# iomodul2.net
KiCad netlist of a schematic drawn in EAGLE
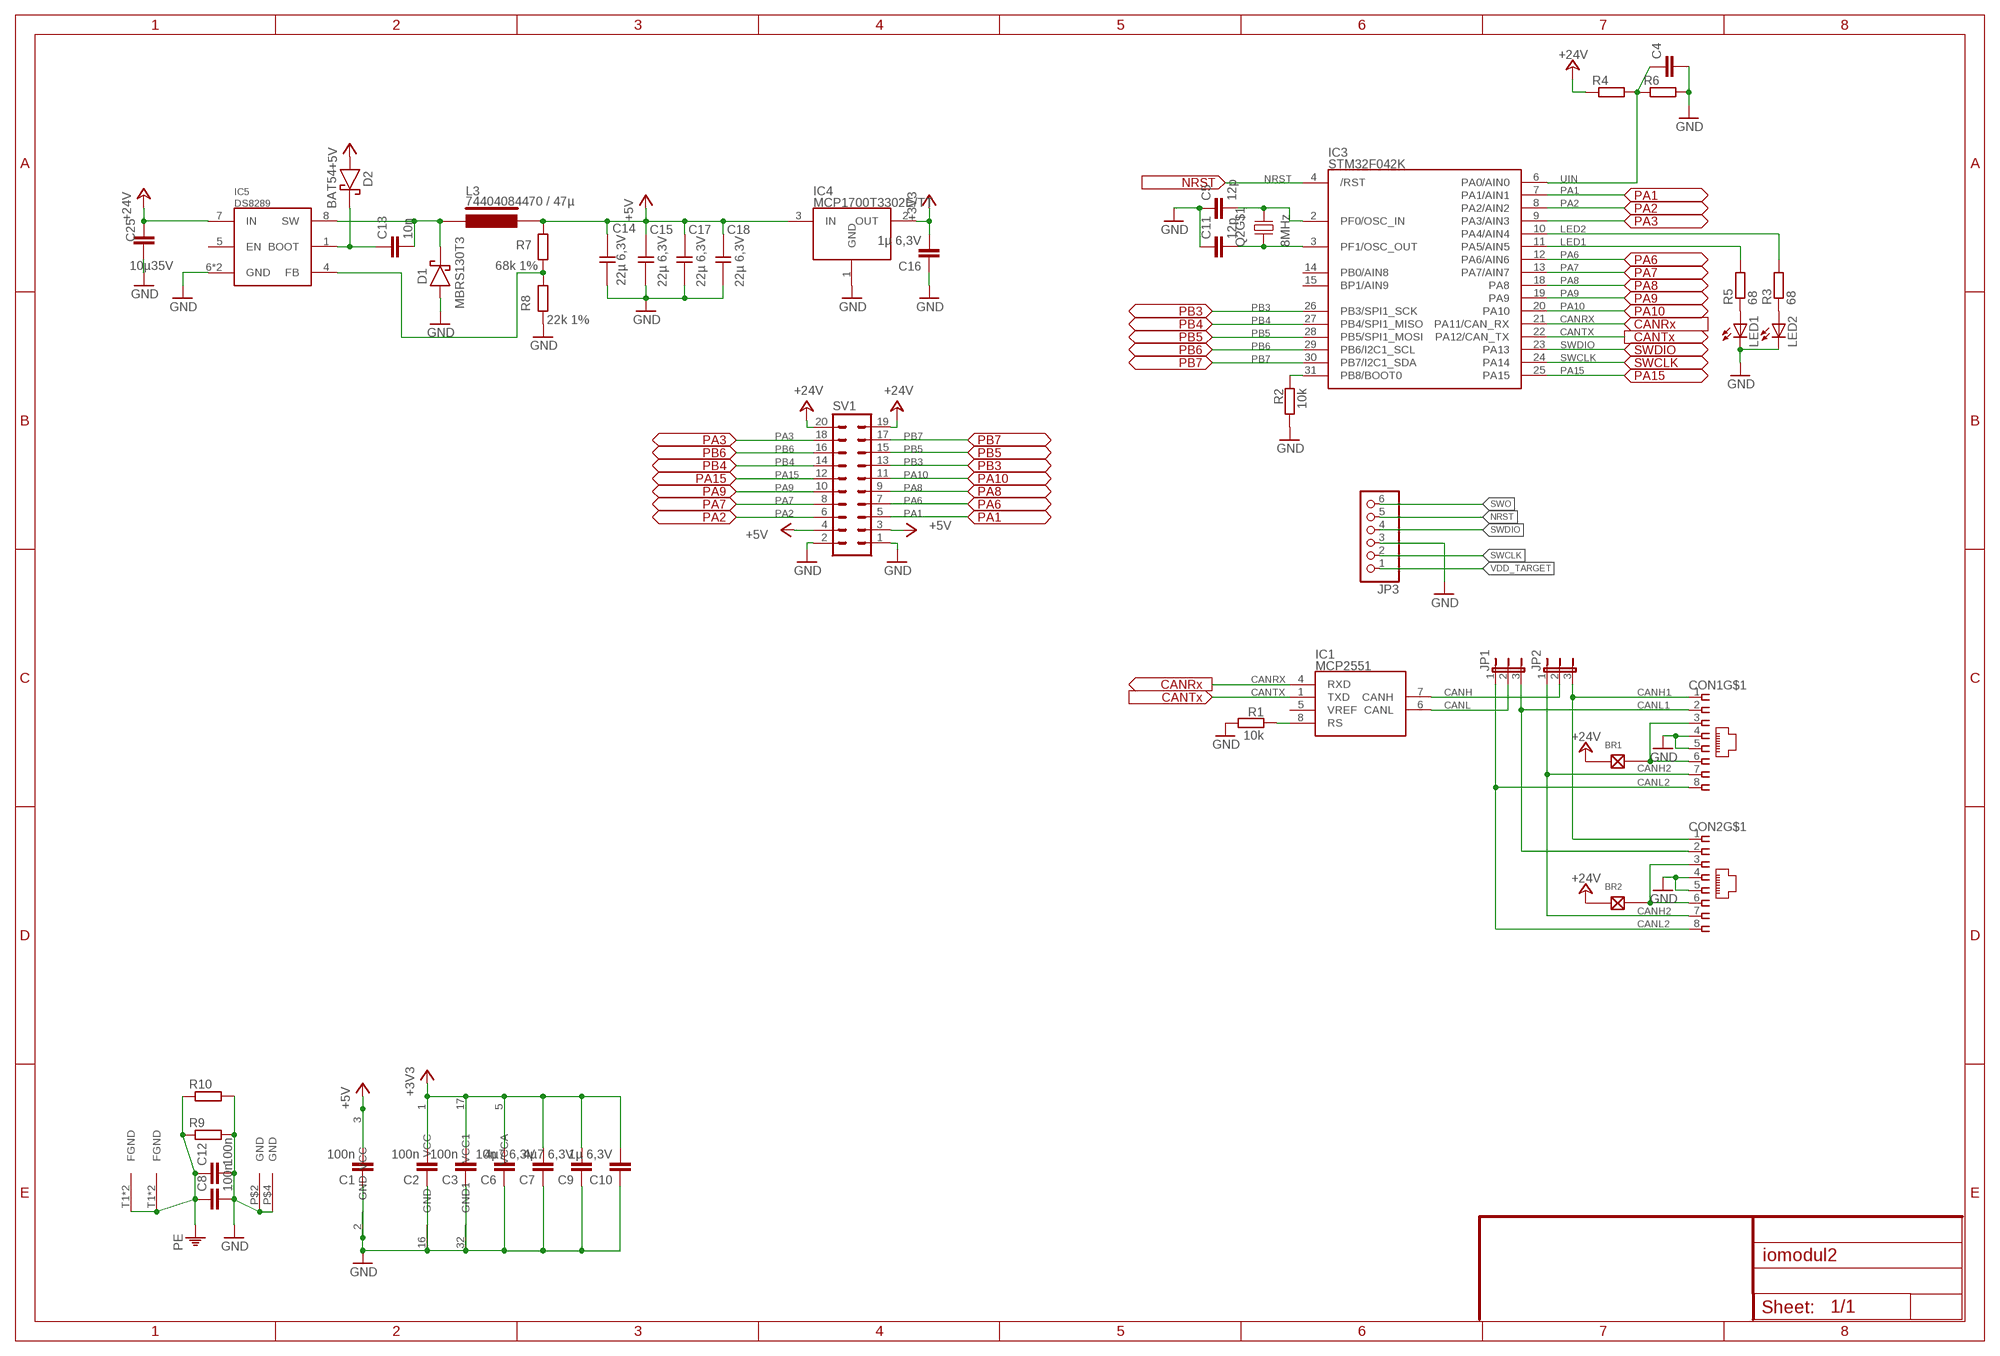
[diagram p0: schematic, sheet 1]

(export (version "E")
  (design (tool "Eeschema 10.0.6"))
  (components
    (comp (ref "BR1")
      (value "LÖTBRÜCKE-S")
      (footprint "eagle-import:LÖTBRÜCKE")
      (libsource (lib "eagle-import") (part "LÖTBRÜCKE-S"))
    )
    (comp (ref "BR2")
      (value "LÖTBRÜCKE-S")
      (footprint "eagle-import:LÖTBRÜCKE")
      (libsource (lib "eagle-import") (part "LÖTBRÜCKE-S"))
    )
    (comp (ref "C1")
      (value "100n")
      (footprint "eagle-import:C1206")
      (libsource (lib "eagle-import") (part "C-EUC1206"))
    )
    (comp (ref "C2")
      (value "100n")
      (footprint "eagle-import:C1206")
      (libsource (lib "eagle-import") (part "C-EUC1206"))
    )
    (comp (ref "C3")
      (value "100n")
      (footprint "eagle-import:C1206")
      (libsource (lib "eagle-import") (part "C-EUC1206"))
    )
    (comp (ref "C4")
      (value "C-EUC1206")
      (footprint "eagle-import:C1206")
      (libsource (lib "eagle-import") (part "C-EUC1206"))
    )
    (comp (ref "C5")
      (value "12p")
      (footprint "eagle-import:C1206")
      (libsource (lib "eagle-import") (part "C-EUC1206"))
    )
    (comp (ref "C6")
      (value "10n")
      (footprint "eagle-import:C1206")
      (libsource (lib "eagle-import") (part "C-EUC1206"))
    )
    (comp (ref "C7")
      (value "4µ7 6,3V")
      (footprint "eagle-import:C1206")
      (libsource (lib "eagle-import") (part "C-EUC1206"))
    )
    (comp (ref "C8")
      (value "100n")
      (footprint "eagle-import:C1206")
      (libsource (lib "eagle-import") (part "C-EUC1206"))
    )
    (comp (ref "C9")
      (value "4µ7 6,3V")
      (footprint "eagle-import:C1206")
      (libsource (lib "eagle-import") (part "C-EUC1206"))
    )
    (comp (ref "C10")
      (value "1µ 6,3V")
      (footprint "eagle-import:C1206")
      (libsource (lib "eagle-import") (part "C-EUC1206"))
    )
    (comp (ref "C11")
      (value "12p")
      (footprint "eagle-import:C1206")
      (libsource (lib "eagle-import") (part "C-EUC1206"))
    )
    (comp (ref "C12")
      (value "100n")
      (footprint "eagle-import:C1206")
      (libsource (lib "eagle-import") (part "C-EUC1206"))
    )
    (comp (ref "C13")
      (value "10n")
      (footprint "eagle-import:C1206")
      (libsource (lib "eagle-import") (part "C-EUC1206"))
    )
    (comp (ref "C14")
      (value "22µ 6,3V")
      (footprint "eagle-import:1210")
      (libsource (lib "eagle-import") (part "CAP1210"))
    )
    (comp (ref "C15")
      (value "22µ 6,3V")
      (footprint "eagle-import:1210")
      (libsource (lib "eagle-import") (part "CAP1210"))
    )
    (comp (ref "C16")
      (value "1µ 6,3V")
      (footprint "eagle-import:C1206")
      (libsource (lib "eagle-import") (part "C-EUC1206"))
    )
    (comp (ref "C17")
      (value "22µ 6,3V")
      (footprint "eagle-import:1210")
      (libsource (lib "eagle-import") (part "CAP1210"))
    )
    (comp (ref "C18")
      (value "22µ 6,3V")
      (footprint "eagle-import:1210")
      (libsource (lib "eagle-import") (part "CAP1210"))
    )
    (comp (ref "C25")
      (value "10µ35V")
      (footprint "eagle-import:C1206")
      (libsource (lib "eagle-import") (part "C-EUC1206"))
    )
    (comp (ref "CON1")
      (value "MEBP_8-8G")
      (footprint "eagle-import:MEBP")
      (libsource (lib "eagle-import") (part "MEBP_8-8G"))
    )
    (comp (ref "CON2")
      (value "MEBP_8-8G")
      (footprint "eagle-import:MEBP")
      (libsource (lib "eagle-import") (part "MEBP_8-8G"))
    )
    (comp (ref "D1")
      (value "MBRS130T3")
      (footprint "eagle-import:SMB")
      (libsource (lib "eagle-import") (part "MBRS130T3"))
    )
    (comp (ref "D2")
      (value "BAT54")
      (footprint "eagle-import:SOT23_32")
      (libsource (lib "eagle-import") (part "BAT54"))
    )
    (comp (ref "IC1")
      (value "MCP2551")
      (footprint "eagle-import:SO-8")
      (libsource (lib "eagle-import") (part "MCP2551"))
    )
    (comp (ref "IC3")
      (value "STM32F042K")
      (footprint "eagle-import:LQFP32")
      (libsource (lib "eagle-import") (part "STM32F042"))
    )
    (comp (ref "IC4")
      (value "MCP1700T3302E/TT")
      (footprint "eagle-import:SOT23")
      (libsource (lib "eagle-import") (part "MCP1700"))
    )
    (comp (ref "IC5")
      (value "DS8289")
      (footprint "eagle-import:SO8-POWERPAD")
      (libsource (lib "eagle-import") (part "DS8289"))
    )
    (comp (ref "JP1")
      (value "JP2E")
      (footprint "eagle-import:JP2")
      (libsource (lib "eagle-import") (part "JP2E"))
    )
    (comp (ref "JP2")
      (value "JP2E")
      (footprint "eagle-import:JP2")
      (libsource (lib "eagle-import") (part "JP2E"))
    )
    (comp (ref "JP3")
      (value "PINHD-1X6")
      (footprint "eagle-import:1X06")
      (libsource (lib "eagle-import") (part "PINHD-1X6"))
    )
    (comp (ref "L3")
      (value "74404084470 / 47µ")
      (footprint "eagle-import:WE-LQS")
      (libsource (lib "eagle-import") (part "WE-LQS"))
    )
    (comp (ref "LED1")
      (value "LEDCHIPLED_0603")
      (footprint "eagle-import:CHIPLED_0603")
      (libsource (lib "eagle-import") (part "LEDCHIPLED_0603"))
    )
    (comp (ref "LED2")
      (value "LEDCHIPLED_0603")
      (footprint "eagle-import:CHIPLED_0603")
      (libsource (lib "eagle-import") (part "LEDCHIPLED_0603"))
    )
    (comp (ref "Q2")
      (value "8MHz")
      (footprint "eagle-import:MT-CRYSTAL")
      (libsource (lib "eagle-import") (part "MT-CRYSTAL"))
    )
    (comp (ref "R1")
      (value "10k")
      (footprint "eagle-import:R1206")
      (libsource (lib "eagle-import") (part "R-EU_R1206"))
    )
    (comp (ref "R2")
      (value "10k")
      (footprint "eagle-import:R1206")
      (libsource (lib "eagle-import") (part "R-EU_R1206"))
    )
    (comp (ref "R3")
      (value "68")
      (footprint "eagle-import:R1206")
      (libsource (lib "eagle-import") (part "R-EU_R1206"))
    )
    (comp (ref "R4")
      (value "R-EU_R1206")
      (footprint "eagle-import:R1206")
      (libsource (lib "eagle-import") (part "R-EU_R1206"))
    )
    (comp (ref "R5")
      (value "68")
      (footprint "eagle-import:R1206")
      (libsource (lib "eagle-import") (part "R-EU_R1206"))
    )
    (comp (ref "R6")
      (value "R-EU_R1206")
      (footprint "eagle-import:R1206")
      (libsource (lib "eagle-import") (part "R-EU_R1206"))
    )
    (comp (ref "R7")
      (value "68k 1%")
      (footprint "eagle-import:R1206")
      (libsource (lib "eagle-import") (part "R-EU_R1206"))
    )
    (comp (ref "R8")
      (value "22k 1%")
      (footprint "eagle-import:R1206")
      (libsource (lib "eagle-import") (part "R-EU_R1206"))
    )
    (comp (ref "R9")
      (value "R-EU_R1206")
      (footprint "eagle-import:R1206")
      (libsource (lib "eagle-import") (part "R-EU_R1206"))
    )
    (comp (ref "R10")
      (value "R-EU_R1206")
      (footprint "eagle-import:R1206")
      (libsource (lib "eagle-import") (part "R-EU_R1206"))
    )
    (comp (ref "SV1")
      (value "MA10-2")
      (footprint "eagle-import:MA10-2")
      (libsource (lib "eagle-import") (part "MA10-2"))
    )
  )
  (nets
    (net (code "1") (name "+3V3") (class "Default")
      (node (ref "C10") (pin "2") (pinfunction "2_2") (pintype "passive"))
      (node (ref "C16") (pin "2") (pinfunction "2_2") (pintype "passive"))
      (node (ref "C2") (pin "2") (pinfunction "2_2") (pintype "passive"))
      (node (ref "C3") (pin "2") (pinfunction "2_2") (pintype "passive"))
      (node (ref "C6") (pin "2") (pinfunction "2_2") (pintype "passive"))
      (node (ref "C7") (pin "2") (pinfunction "2_2") (pintype "passive"))
      (node (ref "C9") (pin "2") (pinfunction "2_2") (pintype "passive"))
      (node (ref "IC3") (pin "1") (pinfunction "VCC_1") (pintype "power_in"))
      (node (ref "IC3") (pin "17") (pinfunction "VCC1_17") (pintype "power_in"))
      (node (ref "IC3") (pin "5") (pinfunction "VCCA_5") (pintype "power_in"))
      (node (ref "IC4") (pin "2") (pinfunction "OUT_2") (pintype "power_in"))
    )
    (net (code "2") (name "+5V") (class "Default")
      (node (ref "C1") (pin "2") (pinfunction "2_2") (pintype "passive"))
      (node (ref "C14") (pin "2") (pinfunction "2_2") (pintype "passive"))
      (node (ref "C15") (pin "2") (pinfunction "2_2") (pintype "passive"))
      (node (ref "C17") (pin "2") (pinfunction "2_2") (pintype "passive"))
      (node (ref "C18") (pin "2") (pinfunction "2_2") (pintype "passive"))
      (node (ref "D2") (pin "1") (pinfunction "A_1") (pintype "passive"))
      (node (ref "IC1") (pin "3") (pinfunction "VCC_3") (pintype "power_in"))
      (node (ref "IC4") (pin "3") (pinfunction "IN_3") (pintype "power_in"))
      (node (ref "L3") (pin "P$2") (pinfunction "P$2_P$2") (pintype "passive"))
      (node (ref "R7") (pin "2") (pinfunction "2_2") (pintype "passive"))
      (node (ref "SV1") (pin "3") (pinfunction "3_3") (pintype "passive"))
      (node (ref "SV1") (pin "4") (pinfunction "4_4") (pintype "passive"))
    )
    (net (code "3") (name "+24V") (class "Default")
      (node (ref "BR1") (pin "1") (pinfunction "1_1") (pintype "passive"))
      (node (ref "BR2") (pin "1") (pinfunction "1_1") (pintype "passive"))
      (node (ref "C25") (pin "2") (pinfunction "2_2") (pintype "passive"))
      (node (ref "IC5") (pin "7") (pinfunction "IN_7") (pintype "power_in"))
      (node (ref "R4") (pin "1") (pinfunction "1_1") (pintype "passive"))
      (node (ref "SV1") (pin "19") (pinfunction "19_19") (pintype "passive"))
      (node (ref "SV1") (pin "20") (pinfunction "20_20") (pintype "passive"))
    )
    (net (code "4") (name "/CANH") (class "Default")
      (node (ref "IC1") (pin "7") (pinfunction "CANH_7") (pintype "bidirectional"))
      (node (ref "JP2") (pin "2") (pinfunction "2_2") (pintype "passive"))
    )
    (net (code "5") (name "/CANH1") (class "Default")
      (node (ref "CON1") (pin "1") (pinfunction "1_1") (pintype "passive"))
      (node (ref "CON2") (pin "1") (pinfunction "1_1") (pintype "passive"))
      (node (ref "JP2") (pin "3") (pinfunction "3_3") (pintype "passive"))
    )
    (net (code "6") (name "/CANH2") (class "Default")
      (node (ref "CON1") (pin "7") (pinfunction "7_7") (pintype "passive"))
      (node (ref "CON2") (pin "7") (pinfunction "7_7") (pintype "passive"))
      (node (ref "JP2") (pin "1") (pinfunction "1_1") (pintype "passive"))
    )
    (net (code "7") (name "/CANL") (class "Default")
      (node (ref "IC1") (pin "6") (pinfunction "CANL_6") (pintype "bidirectional"))
      (node (ref "JP1") (pin "2") (pinfunction "2_2") (pintype "passive"))
    )
    (net (code "8") (name "/CANL1") (class "Default")
      (node (ref "CON1") (pin "2") (pinfunction "2_2") (pintype "passive"))
      (node (ref "CON2") (pin "2") (pinfunction "2_2") (pintype "passive"))
      (node (ref "JP1") (pin "3") (pinfunction "3_3") (pintype "passive"))
    )
    (net (code "9") (name "/CANL2") (class "Default")
      (node (ref "CON1") (pin "8") (pinfunction "8_8") (pintype "passive"))
      (node (ref "CON2") (pin "8") (pinfunction "8_8") (pintype "passive"))
      (node (ref "JP1") (pin "1") (pinfunction "1_1") (pintype "passive"))
    )
    (net (code "10") (name "/CANRX") (class "Default")
      (node (ref "IC1") (pin "4") (pinfunction "RXD_4") (pintype "bidirectional"))
      (node (ref "IC3") (pin "21") (pinfunction "PA11/CAN_RX_21") (pintype "bidirectional"))
    )
    (net (code "11") (name "/CANTX") (class "Default")
      (node (ref "IC1") (pin "1") (pinfunction "TXD_1") (pintype "bidirectional"))
      (node (ref "IC3") (pin "22") (pinfunction "PA12/CAN_TX_22") (pintype "bidirectional"))
    )
    (net (code "12") (name "/LED1") (class "Default")
      (node (ref "IC3") (pin "11") (pinfunction "PA5/AIN5_11") (pintype "bidirectional"))
      (node (ref "R5") (pin "2") (pinfunction "2_2") (pintype "passive"))
    )
    (net (code "13") (name "/LED2") (class "Default")
      (node (ref "IC3") (pin "10") (pinfunction "PA4/AIN4_10") (pintype "bidirectional"))
      (node (ref "R3") (pin "2") (pinfunction "2_2") (pintype "passive"))
    )
    (net (code "14") (name "/PA1") (class "Default")
      (node (ref "IC3") (pin "7") (pinfunction "PA1/AIN1_7") (pintype "bidirectional"))
      (node (ref "SV1") (pin "5") (pinfunction "5_5") (pintype "passive"))
    )
    (net (code "15") (name "/PA2") (class "Default")
      (node (ref "IC3") (pin "8") (pinfunction "PA2/AIN2_8") (pintype "bidirectional"))
      (node (ref "SV1") (pin "6") (pinfunction "6_6") (pintype "passive"))
    )
    (net (code "16") (name "/PA3") (class "Default")
      (node (ref "IC3") (pin "9") (pinfunction "PA3/AIN3_9") (pintype "bidirectional"))
      (node (ref "SV1") (pin "18") (pinfunction "18_18") (pintype "passive"))
    )
    (net (code "17") (name "/PA6") (class "Default")
      (node (ref "IC3") (pin "12") (pinfunction "PA6/AIN6_12") (pintype "bidirectional"))
      (node (ref "SV1") (pin "7") (pinfunction "7_7") (pintype "passive"))
    )
    (net (code "18") (name "/PA7") (class "Default")
      (node (ref "IC3") (pin "13") (pinfunction "PA7/AIN7_13") (pintype "bidirectional"))
      (node (ref "SV1") (pin "8") (pinfunction "8_8") (pintype "passive"))
    )
    (net (code "19") (name "/PA8") (class "Default")
      (node (ref "IC3") (pin "18") (pinfunction "PA8_18") (pintype "bidirectional"))
      (node (ref "SV1") (pin "9") (pinfunction "9_9") (pintype "passive"))
    )
    (net (code "20") (name "/PA9") (class "Default")
      (node (ref "IC3") (pin "19") (pinfunction "PA9_19") (pintype "bidirectional"))
      (node (ref "SV1") (pin "10") (pinfunction "10_10") (pintype "passive"))
    )
    (net (code "21") (name "/PA10") (class "Default")
      (node (ref "IC3") (pin "20") (pinfunction "PA10_20") (pintype "bidirectional"))
      (node (ref "SV1") (pin "11") (pinfunction "11_11") (pintype "passive"))
    )
    (net (code "22") (name "/PA15") (class "Default")
      (node (ref "IC3") (pin "25") (pinfunction "PA15_25") (pintype "bidirectional"))
      (node (ref "SV1") (pin "12") (pinfunction "12_12") (pintype "passive"))
    )
    (net (code "23") (name "/PB3") (class "Default")
      (node (ref "IC3") (pin "26") (pinfunction "PB3/SPI1_SCK_26") (pintype "bidirectional"))
      (node (ref "SV1") (pin "13") (pinfunction "13_13") (pintype "passive"))
    )
    (net (code "24") (name "/PB4") (class "Default")
      (node (ref "IC3") (pin "27") (pinfunction "PB4/SPI1_MISO_27") (pintype "bidirectional"))
      (node (ref "SV1") (pin "14") (pinfunction "14_14") (pintype "passive"))
    )
    (net (code "25") (name "/PB5") (class "Default")
      (node (ref "IC3") (pin "28") (pinfunction "PB5/SPI1_MOSI_28") (pintype "bidirectional"))
      (node (ref "SV1") (pin "15") (pinfunction "15_15") (pintype "passive"))
    )
    (net (code "26") (name "/PB6") (class "Default")
      (node (ref "IC3") (pin "29") (pinfunction "PB6/I2C1_SCL_29") (pintype "bidirectional"))
      (node (ref "SV1") (pin "16") (pinfunction "16_16") (pintype "passive"))
    )
    (net (code "27") (name "/PB7") (class "Default")
      (node (ref "IC3") (pin "30") (pinfunction "PB7/I2C1_SDA_30") (pintype "bidirectional"))
      (node (ref "SV1") (pin "17") (pinfunction "17_17") (pintype "passive"))
    )
    (net (code "28") (name "/UIN") (class "Default")
      (node (ref "C4") (pin "1") (pinfunction "1_1") (pintype "passive"))
      (node (ref "IC3") (pin "6") (pinfunction "PA0/AIN0_6") (pintype "bidirectional"))
      (node (ref "R4") (pin "2") (pinfunction "2_2") (pintype "passive"))
      (node (ref "R6") (pin "1") (pinfunction "1_1") (pintype "passive"))
    )
    (net (code "29") (name "GND") (class "Default")
      (node (ref "C1") (pin "1") (pinfunction "1_1") (pintype "passive"))
      (node (ref "C10") (pin "1") (pinfunction "1_1") (pintype "passive"))
      (node (ref "C11") (pin "1") (pinfunction "1_1") (pintype "passive"))
      (node (ref "C12") (pin "2") (pinfunction "2_2") (pintype "passive"))
      (node (ref "C14") (pin "1") (pinfunction "1_1") (pintype "passive"))
      (node (ref "C15") (pin "1") (pinfunction "1_1") (pintype "passive"))
      (node (ref "C16") (pin "1") (pinfunction "1_1") (pintype "passive"))
      (node (ref "C17") (pin "1") (pinfunction "1_1") (pintype "passive"))
      (node (ref "C18") (pin "1") (pinfunction "1_1") (pintype "passive"))
      (node (ref "C2") (pin "1") (pinfunction "1_1") (pintype "passive"))
      (node (ref "C25") (pin "1") (pinfunction "1_1") (pintype "passive"))
      (node (ref "C3") (pin "1") (pinfunction "1_1") (pintype "passive"))
      (node (ref "C4") (pin "2") (pinfunction "2_2") (pintype "passive"))
      (node (ref "C5") (pin "1") (pinfunction "1_1") (pintype "passive"))
      (node (ref "C6") (pin "1") (pinfunction "1_1") (pintype "passive"))
      (node (ref "C7") (pin "1") (pinfunction "1_1") (pintype "passive"))
      (node (ref "C8") (pin "2") (pinfunction "2_2") (pintype "passive"))
      (node (ref "C9") (pin "1") (pinfunction "1_1") (pintype "passive"))
      (node (ref "CON1") (pin "4") (pinfunction "4_4") (pintype "passive"))
      (node (ref "CON1") (pin "5") (pinfunction "5_5") (pintype "passive"))
      (node (ref "CON2") (pin "4") (pinfunction "4_4") (pintype "passive"))
      (node (ref "CON2") (pin "5") (pinfunction "5_5") (pintype "passive"))
      (node (ref "D1") (pin "A") (pinfunction "A_A") (pintype "passive"))
      (node (ref "IC1") (pin "2") (pinfunction "GND_2") (pintype "power_in"))
      (node (ref "IC3") (pin "16") (pinfunction "GND_16") (pintype "power_in"))
      (node (ref "IC3") (pin "32") (pinfunction "GND1_32") (pintype "power_in"))
      (node (ref "IC4") (pin "1") (pinfunction "GND_1") (pintype "power_in"))
      (node (ref "IC5") (pin "6") (pinfunction "GND_6") (pintype "power_in"))
      (node (ref "IC5") (pin "TP") (pinfunction "GND_TP") (pintype "power_in"))
      (node (ref "JP3") (pin "3") (pinfunction "3_3") (pintype "passive"))
      (node (ref "LED1") (pin "C") (pinfunction "C_C") (pintype "passive"))
      (node (ref "LED2") (pin "C") (pinfunction "C_C") (pintype "passive"))
      (node (ref "Q2") (pin "P$2") (pinfunction "GND_P$2") (pintype "power_in"))
      (node (ref "Q2") (pin "P$4") (pinfunction "GND_P$4") (pintype "power_in"))
      (node (ref "R1") (pin "2") (pinfunction "2_2") (pintype "passive"))
      (node (ref "R10") (pin "2") (pinfunction "2_2") (pintype "passive"))
      (node (ref "R2") (pin "2") (pinfunction "2_2") (pintype "passive"))
      (node (ref "R6") (pin "2") (pinfunction "2_2") (pintype "passive"))
      (node (ref "R8") (pin "1") (pinfunction "1_1") (pintype "passive"))
      (node (ref "R9") (pin "2") (pinfunction "2_2") (pintype "passive"))
      (node (ref "SV1") (pin "1") (pinfunction "1_1") (pintype "passive"))
      (node (ref "SV1") (pin "2") (pinfunction "2_2") (pintype "passive"))
    )
    (net (code "30") (name "NRST") (class "Default")
      (node (ref "IC3") (pin "4") (pinfunction "/RST_4") (pintype "bidirectional"))
      (node (ref "JP3") (pin "5") (pinfunction "5_5") (pintype "passive"))
    )
    (net (code "31") (name "Net-(BR1-Pad2)") (class "Default")
      (node (ref "BR1") (pin "2") (pinfunction "2_2") (pintype "passive"))
      (node (ref "CON1") (pin "3") (pinfunction "3_3") (pintype "passive"))
      (node (ref "CON1") (pin "6") (pinfunction "6_6") (pintype "passive"))
    )
    (net (code "32") (name "Net-(BR2-Pad2)") (class "Default")
      (node (ref "BR2") (pin "2") (pinfunction "2_2") (pintype "passive"))
      (node (ref "CON2") (pin "3") (pinfunction "3_3") (pintype "passive"))
      (node (ref "CON2") (pin "6") (pinfunction "6_6") (pintype "passive"))
    )
    (net (code "33") (name "Net-(D2-K)") (class "Default")
      (node (ref "C13") (pin "1") (pinfunction "1_1") (pintype "passive"))
      (node (ref "D2") (pin "3") (pinfunction "K_3") (pintype "passive"))
      (node (ref "IC5") (pin "1") (pinfunction "BOOT_1") (pintype "power_in"))
    )
    (net (code "34") (name "Net-(IC1A-RS)") (class "Default")
      (node (ref "IC1") (pin "8") (pinfunction "RS_8") (pintype "bidirectional"))
      (node (ref "R1") (pin "1") (pinfunction "1_1") (pintype "passive"))
    )
    (net (code "35") (name "Net-(IC3A-PB8{slash}BOOT0)") (class "Default")
      (node (ref "IC3") (pin "31") (pinfunction "PB8/BOOT0_31") (pintype "bidirectional"))
      (node (ref "R2") (pin "1") (pinfunction "1_1") (pintype "passive"))
    )
    (net (code "36") (name "Net-(IC3A-PF0{slash}OSC_IN)") (class "Default")
      (node (ref "C5") (pin "2") (pinfunction "2_2") (pintype "passive"))
      (node (ref "IC3") (pin "2") (pinfunction "PF0/OSC_IN_2") (pintype "bidirectional"))
      (node (ref "Q2") (pin "P$3") (pinfunction "2_P$3") (pintype "passive"))
    )
    (net (code "37") (name "Net-(IC3A-PF1{slash}OSC_OUT)") (class "Default")
      (node (ref "C11") (pin "2") (pinfunction "2_2") (pintype "passive"))
      (node (ref "IC3") (pin "3") (pinfunction "PF1/OSC_OUT_3") (pintype "bidirectional"))
      (node (ref "Q2") (pin "P$1") (pinfunction "1_P$1") (pintype "passive"))
    )
    (net (code "38") (name "Net-(IC5-FB)") (class "Default")
      (node (ref "IC5") (pin "4") (pinfunction "FB_4") (pintype "input"))
      (node (ref "R7") (pin "1") (pinfunction "1_1") (pintype "passive"))
      (node (ref "R8") (pin "2") (pinfunction "2_2") (pintype "passive"))
    )
    (net (code "39") (name "Net-(IC5-SW)") (class "Default")
      (node (ref "C13") (pin "2") (pinfunction "2_2") (pintype "passive"))
      (node (ref "D1") (pin "K") (pinfunction "K_K") (pintype "passive"))
      (node (ref "IC5") (pin "8") (pinfunction "SW_8") (pintype "power_in"))
      (node (ref "L3") (pin "P$1") (pinfunction "P$1_P$1") (pintype "passive"))
    )
    (net (code "40") (name "Net-(LED1-PadA)") (class "Default")
      (node (ref "LED1") (pin "A") (pinfunction "A_A") (pintype "passive"))
      (node (ref "R5") (pin "1") (pinfunction "1_1") (pintype "passive"))
    )
    (net (code "41") (name "Net-(LED2-PadA)") (class "Default")
      (node (ref "LED2") (pin "A") (pinfunction "A_A") (pintype "passive"))
      (node (ref "R3") (pin "1") (pinfunction "1_1") (pintype "passive"))
    )
    (net (code "42") (name "PE") (class "Default")
      (node (ref "C12") (pin "1") (pinfunction "1_1") (pintype "passive"))
      (node (ref "C8") (pin "1") (pinfunction "1_1") (pintype "passive"))
      (node (ref "CON1") (pin "T1") (pinfunction "FGND_T1") (pintype "power_in"))
      (node (ref "CON1") (pin "T2") (pinfunction "FGND_T2") (pintype "power_in"))
      (node (ref "CON2") (pin "T1") (pinfunction "FGND_T1") (pintype "power_in"))
      (node (ref "CON2") (pin "T2") (pinfunction "FGND_T2") (pintype "power_in"))
      (node (ref "R10") (pin "1") (pinfunction "1_1") (pintype "passive"))
      (node (ref "R9") (pin "1") (pinfunction "1_1") (pintype "passive"))
    )
    (net (code "43") (name "SWCLK") (class "Default")
      (node (ref "IC3") (pin "24") (pinfunction "PA14_24") (pintype "bidirectional"))
      (node (ref "JP3") (pin "2") (pinfunction "2_2") (pintype "passive"))
    )
    (net (code "44") (name "SWDIO") (class "Default")
      (node (ref "IC3") (pin "23") (pinfunction "PA13_23") (pintype "bidirectional"))
      (node (ref "JP3") (pin "4") (pinfunction "4_4") (pintype "passive"))
    )
    (net (code "45") (name "SWO") (class "Default")
      (node (ref "JP3") (pin "6") (pinfunction "6_6") (pintype "passive"))
    )
    (net (code "46") (name "VDD_TARGET") (class "Default")
      (node (ref "JP3") (pin "1") (pinfunction "1_1") (pintype "passive"))
    )
    (net (code "47") (name "unconnected-(IC1A-VREF-Pad5)") (class "Default")
      (node (ref "IC1") (pin "5") (pinfunction "VREF_5") (pintype "bidirectional"))
    )
    (net (code "48") (name "unconnected-(IC3A-BP1{slash}AIN9-Pad15)") (class "Default")
      (node (ref "IC3") (pin "15") (pinfunction "BP1/AIN9_15") (pintype "bidirectional"))
    )
    (net (code "49") (name "unconnected-(IC3A-PB0{slash}AIN8-Pad14)") (class "Default")
      (node (ref "IC3") (pin "14") (pinfunction "PB0/AIN8_14") (pintype "bidirectional"))
    )
    (net (code "50") (name "unconnected-(IC5-EN-Pad5)") (class "Default")
      (node (ref "IC5") (pin "5") (pinfunction "EN_5") (pintype "input"))
    )
  )
)
